# Ultraschall_Sensoren_85_SMD.net
KiCad netlist of a schematic drawn in EAGLE
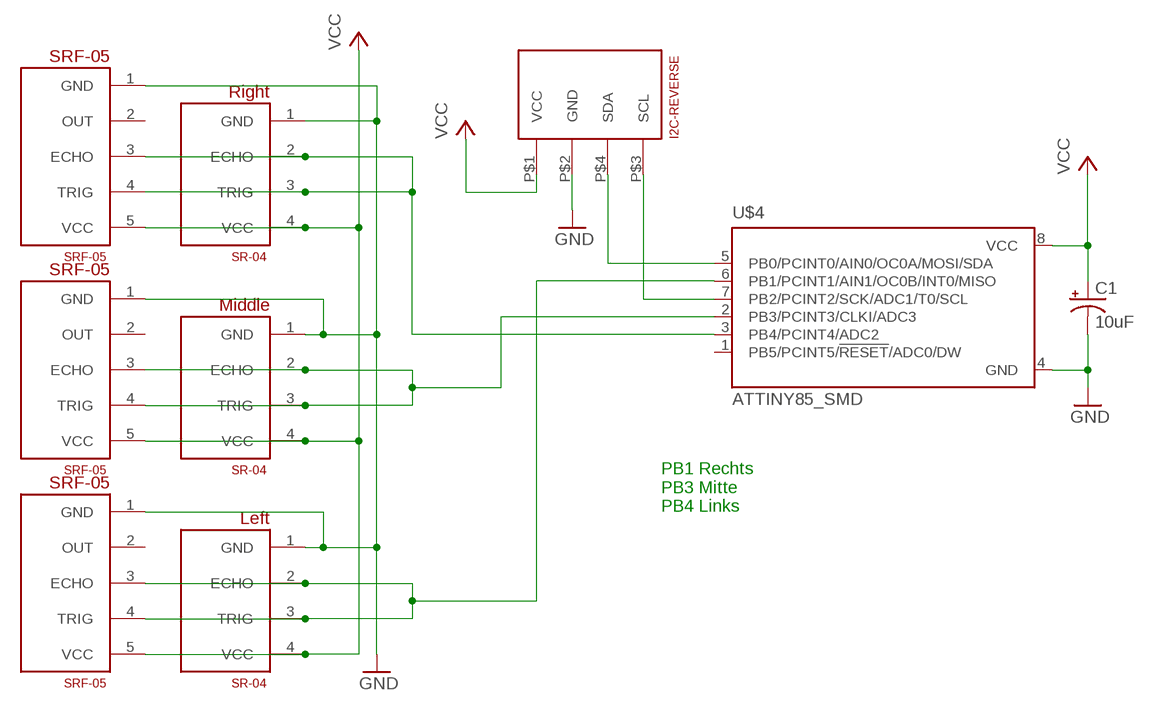
[diagram p0: schematic, sheet 1]

(export (version "E")
  (design (tool "Eeschema 10.0.6"))
  (components
    (comp (ref "C1")
      (value "10uF")
      (footprint "eagle-import:EIA3216")
      (libsource (lib "eagle-import") (part "10UF-TANT"))
    )
    (comp (ref "LINKS")
      (value "Left")
      (footprint "eagle-import:HC-SR04")
      (libsource (lib "eagle-import") (part "SR-04"))
    )
    (comp (ref "MIDDLE")
      (value "Middle")
      (footprint "eagle-import:HC-SR04")
      (libsource (lib "eagle-import") (part "SR-04"))
    )
    (comp (ref "RIGHT")
      (value "Right")
      (footprint "eagle-import:HC-SR04")
      (libsource (lib "eagle-import") (part "SR-04"))
    )
    (comp (ref "U$1")
      (value "SRF-05")
      (footprint "eagle-import:SRF-05")
      (libsource (lib "eagle-import") (part "SRF-05"))
    )
    (comp (ref "U$2")
      (value "I2C-REVERSE")
      (footprint "eagle-import:I2C-CONNECTOR")
      (libsource (lib "eagle-import") (part "I2C-REVERSE"))
    )
    (comp (ref "U$3")
      (value "SRF-05")
      (footprint "eagle-import:SRF-05")
      (libsource (lib "eagle-import") (part "SRF-05"))
    )
    (comp (ref "U$4")
      (value "ATTINY85_SMD")
      (footprint "eagle-import:ATTINY85_SMD")
      (libsource (lib "eagle-import") (part "ATTINY85_SMD"))
    )
    (comp (ref "U$5")
      (value "SRF-05")
      (footprint "eagle-import:SRF-05")
      (libsource (lib "eagle-import") (part "SRF-05"))
    )
  )
  (nets
    (net (code "1") (name "GND") (class "Default")
      (node (ref "C1") (pin "C") (pinfunction "-_C") (pintype "passive"))
      (node (ref "LINKS") (pin "1") (pinfunction "GND_1") (pintype "bidirectional"))
      (node (ref "MIDDLE") (pin "1") (pinfunction "GND_1") (pintype "bidirectional"))
      (node (ref "RIGHT") (pin "1") (pinfunction "GND_1") (pintype "bidirectional"))
      (node (ref "U$1") (pin "1") (pinfunction "GND_1") (pintype "bidirectional"))
      (node (ref "U$2") (pin "P$2") (pinfunction "GND_P$2") (pintype "bidirectional"))
      (node (ref "U$3") (pin "1") (pinfunction "GND_1") (pintype "bidirectional"))
      (node (ref "U$4") (pin "4") (pinfunction "GND_4") (pintype "power_in"))
      (node (ref "U$5") (pin "1") (pinfunction "GND_1") (pintype "bidirectional"))
    )
    (net (code "2") (name "Net-(LINKS-ECHO)") (class "Default")
      (node (ref "LINKS") (pin "2") (pinfunction "ECHO_2") (pintype "bidirectional"))
      (node (ref "LINKS") (pin "3") (pinfunction "TRIG_3") (pintype "bidirectional"))
      (node (ref "U$4") (pin "6") (pinfunction "PB1/PCINT1/AIN1/OC0B/INT0/MISO_6") (pintype "bidirectional"))
      (node (ref "U$5") (pin "3") (pinfunction "ECHO_3") (pintype "bidirectional"))
      (node (ref "U$5") (pin "4") (pinfunction "TRIG_4") (pintype "bidirectional"))
    )
    (net (code "3") (name "Net-(MIDDLE-ECHO)") (class "Default")
      (node (ref "MIDDLE") (pin "2") (pinfunction "ECHO_2") (pintype "bidirectional"))
      (node (ref "MIDDLE") (pin "3") (pinfunction "TRIG_3") (pintype "bidirectional"))
      (node (ref "U$3") (pin "3") (pinfunction "ECHO_3") (pintype "bidirectional"))
      (node (ref "U$3") (pin "4") (pinfunction "TRIG_4") (pintype "bidirectional"))
      (node (ref "U$4") (pin "2") (pinfunction "PB3/PCINT3/CLKI/ADC3_2") (pintype "bidirectional"))
    )
    (net (code "4") (name "Net-(RIGHT-ECHO)") (class "Default")
      (node (ref "RIGHT") (pin "2") (pinfunction "ECHO_2") (pintype "bidirectional"))
      (node (ref "RIGHT") (pin "3") (pinfunction "TRIG_3") (pintype "bidirectional"))
      (node (ref "U$1") (pin "3") (pinfunction "ECHO_3") (pintype "bidirectional"))
      (node (ref "U$1") (pin "4") (pinfunction "TRIG_4") (pintype "bidirectional"))
      (node (ref "U$4") (pin "3") (pinfunction "PB4/PCINT4/ADC2_3") (pintype "bidirectional"))
    )
    (net (code "5") (name "Net-(U$2-SCL)") (class "Default")
      (node (ref "U$2") (pin "P$3") (pinfunction "SCL_P$3") (pintype "bidirectional"))
      (node (ref "U$4") (pin "7") (pinfunction "PB2/PCINT2/SCK/ADC1/T0/SCL_7") (pintype "bidirectional"))
    )
    (net (code "6") (name "Net-(U$2-SDA)") (class "Default")
      (node (ref "U$2") (pin "P$4") (pinfunction "SDA_P$4") (pintype "bidirectional"))
      (node (ref "U$4") (pin "5") (pinfunction "PB0/PCINT0/AIN0/OC0A/MOSI/SDA_5") (pintype "bidirectional"))
    )
    (net (code "7") (name "VCC") (class "Default")
      (node (ref "C1") (pin "A") (pinfunction "+_A") (pintype "passive"))
      (node (ref "LINKS") (pin "4") (pinfunction "VCC_4") (pintype "bidirectional"))
      (node (ref "MIDDLE") (pin "4") (pinfunction "VCC_4") (pintype "bidirectional"))
      (node (ref "RIGHT") (pin "4") (pinfunction "VCC_4") (pintype "bidirectional"))
      (node (ref "U$1") (pin "5") (pinfunction "VCC_5") (pintype "bidirectional"))
      (node (ref "U$2") (pin "P$1") (pinfunction "VCC_P$1") (pintype "bidirectional"))
      (node (ref "U$3") (pin "5") (pinfunction "VCC_5") (pintype "bidirectional"))
      (node (ref "U$4") (pin "8") (pinfunction "VCC_8") (pintype "power_in"))
      (node (ref "U$5") (pin "5") (pinfunction "VCC_5") (pintype "bidirectional"))
    )
    (net (code "8") (name "unconnected-(U$1-OUT-Pad2)") (class "Default")
      (node (ref "U$1") (pin "2") (pinfunction "OUT_2") (pintype "bidirectional"))
    )
    (net (code "9") (name "unconnected-(U$3-OUT-Pad2)") (class "Default")
      (node (ref "U$3") (pin "2") (pinfunction "OUT_2") (pintype "bidirectional"))
    )
    (net (code "10") (name "unconnected-(U$4-PB5{slash}PCINT5{slash}~{RESET}{slash}ADC0{slash}DW-Pad1)") (class "Default")
      (node (ref "U$4") (pin "1") (pinfunction "PB5/PCINT5/~{RESET}/ADC0/DW_1") (pintype "bidirectional"))
    )
    (net (code "11") (name "unconnected-(U$5-OUT-Pad2)") (class "Default")
      (node (ref "U$5") (pin "2") (pinfunction "OUT_2") (pintype "bidirectional"))
    )
  )
)
